# FTWearable.net
KiCad netlist of a schematic drawn in EAGLE
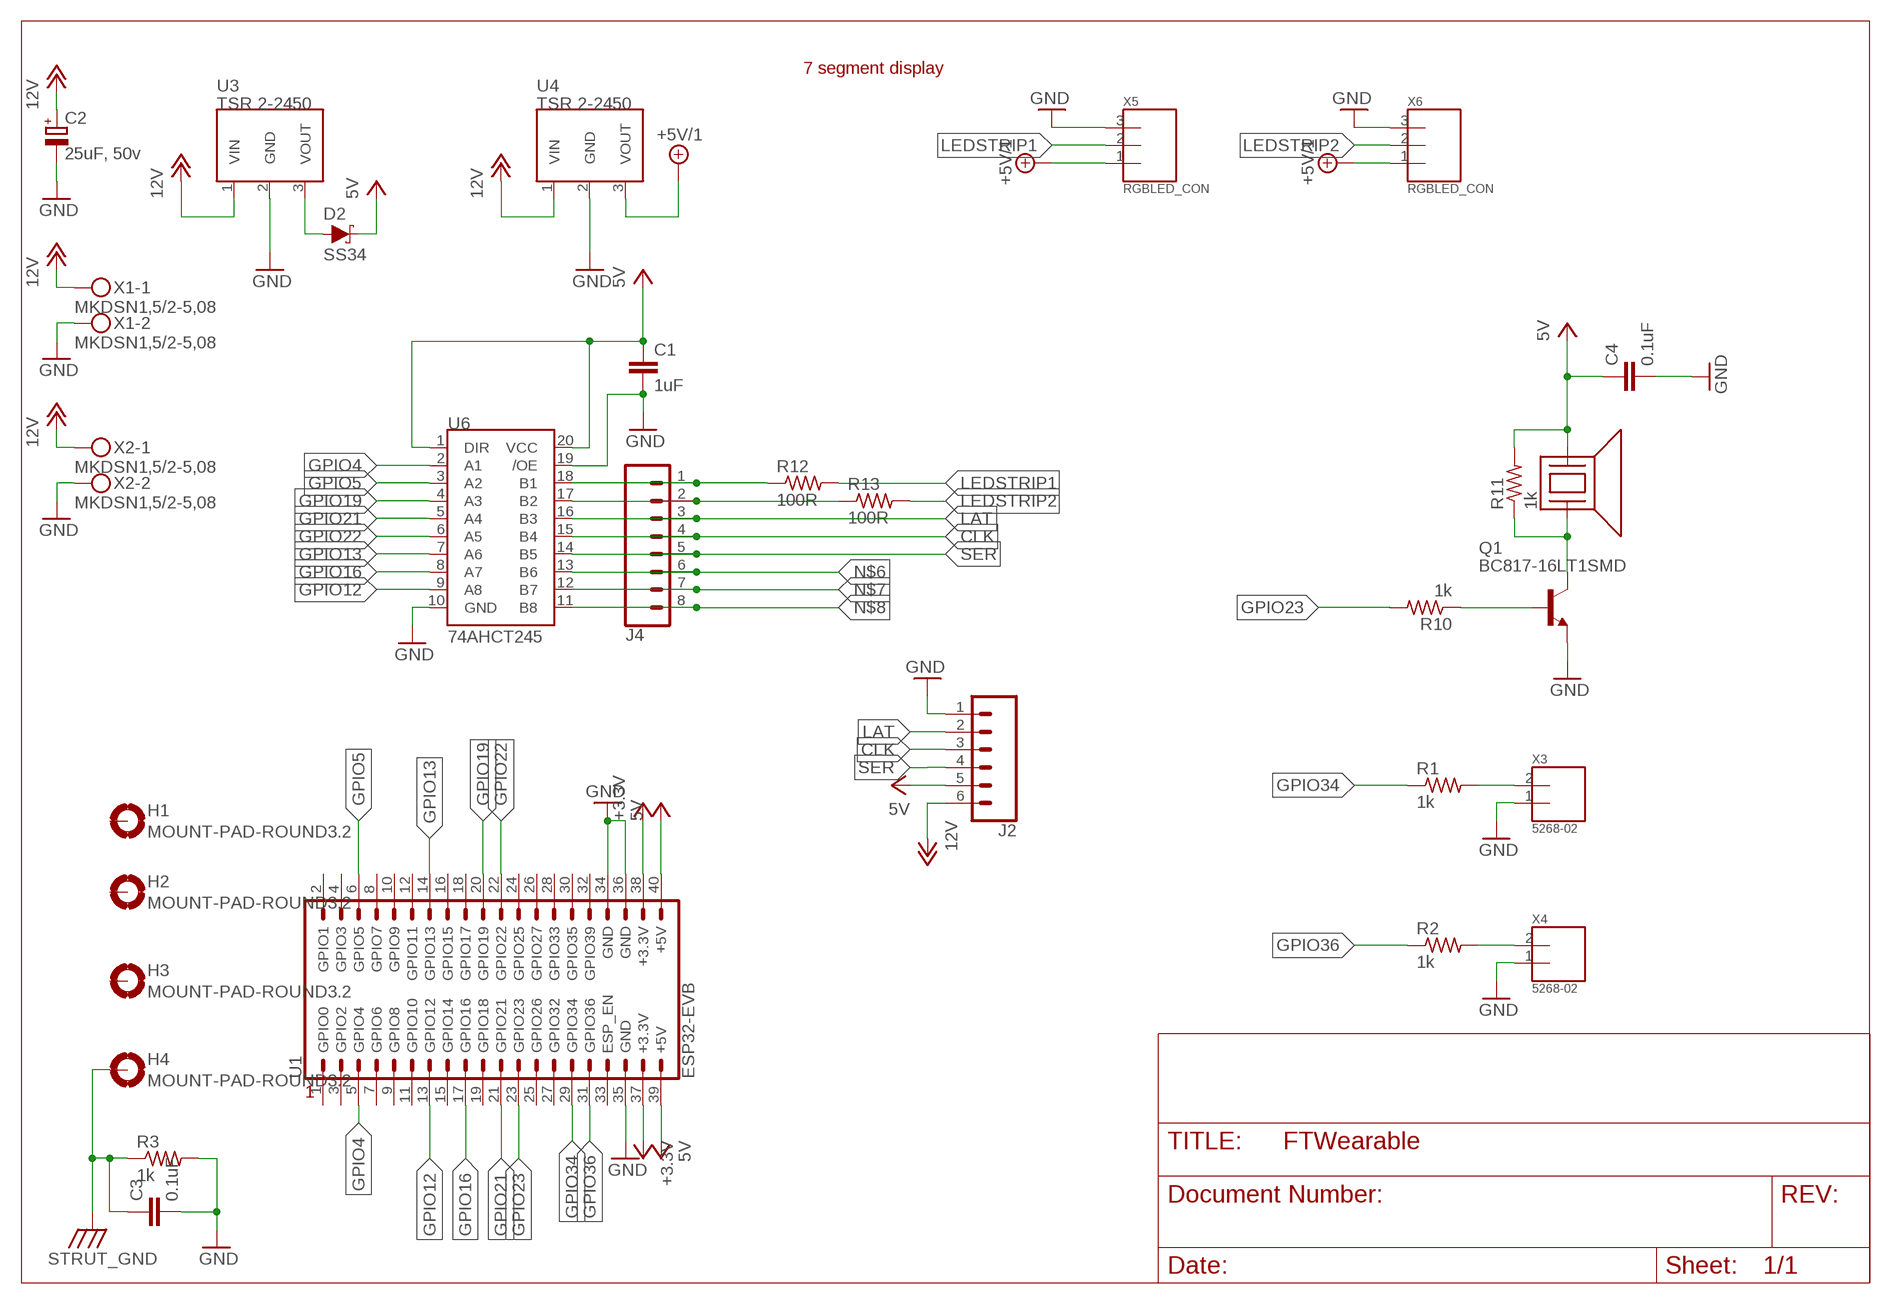
[diagram p0: schematic, sheet 1]

(export (version "E")
  (design (tool "Eeschema 10.0.6"))
  (components
    (comp (ref "C1")
      (value "1uF")
      (footprint "eagle-import:C0805(2012)_LEVEL_A")
      (libsource (lib "eagle-import") (part "C0805(2012)_LEVEL_A"))
    )
    (comp (ref "C2")
      (value "25uF, 50v")
      (footprint "eagle-import:PANASONIC_B_LEVEL_A")
      (libsource (lib "eagle-import") (part "C-POL-PB"))
    )
    (comp (ref "C3")
      (value "0.1uF")
      (footprint "eagle-import:C0603(1608)_LEVEL_A")
      (libsource (lib "eagle-import") (part "C0603(1608)_LEVEL_A"))
    )
    (comp (ref "C4")
      (value "0.1uF")
      (footprint "eagle-import:C0603(1608)_LEVEL_A")
      (libsource (lib "eagle-import") (part "C0603(1608)_LEVEL_A"))
    )
    (comp (ref "D2")
      (value "SS34")
      (footprint "eagle-import:DO-214BA")
      (libsource (lib "eagle-import") (part "DIODE-SCHOTTKY-LSM115JE3"))
    )
    (comp (ref "H1")
      (value "MOUNT-PAD-ROUND3.2")
      (footprint "eagle-import:3,2-PAD")
      (libsource (lib "eagle-import") (part "MOUNT-PAD-ROUND3.2"))
    )
    (comp (ref "H2")
      (value "MOUNT-PAD-ROUND3.2")
      (footprint "eagle-import:3,2-PAD")
      (libsource (lib "eagle-import") (part "MOUNT-PAD-ROUND3.2"))
    )
    (comp (ref "H3")
      (value "MOUNT-PAD-ROUND3.2")
      (footprint "eagle-import:3,2-PAD")
      (libsource (lib "eagle-import") (part "MOUNT-PAD-ROUND3.2"))
    )
    (comp (ref "H4")
      (value "MOUNT-PAD-ROUND3.2")
      (footprint "eagle-import:3,2-PAD")
      (libsource (lib "eagle-import") (part "MOUNT-PAD-ROUND3.2"))
    )
    (comp (ref "J2")
      (value "CONN_06SILK_FEMALE_PTH")
      (footprint "eagle-import:1X06")
      (libsource (lib "eagle-import") (part "CONN_06SILK_FEMALE_PTH"))
    )
    (comp (ref "J4")
      (value "CONN_08\"")
      (footprint "eagle-import:1X08")
      (libsource (lib "eagle-import") (part "CONN_08{dblquote}"))
    )
    (comp (ref "LED1")
      (value "SPARKFUN7SEGMENT")
      (footprint "eagle-import:SPARKFUN7SEGMENT")
      (libsource (lib "eagle-import") (part "SPARKFUN7SEGMENT"))
    )
    (comp (ref "Q1")
      (value "BC817-16LT1SMD")
      (footprint "eagle-import:SOT23-BEC")
      (libsource (lib "eagle-import") (part "BC817SMD-16LT1"))
    )
    (comp (ref "R1")
      (value "1k")
      (footprint "eagle-import:R0603(1608)_LEVEL_A")
      (libsource (lib "eagle-import") (part "R0603(1608)_LEVEL_A"))
    )
    (comp (ref "R2")
      (value "1k")
      (footprint "eagle-import:R0603(1608)_LEVEL_A")
      (libsource (lib "eagle-import") (part "R0603(1608)_LEVEL_A"))
    )
    (comp (ref "R3")
      (value "1k")
      (footprint "eagle-import:R0603(1608)_LEVEL_A")
      (libsource (lib "eagle-import") (part "R0603(1608)_LEVEL_A"))
    )
    (comp (ref "R10")
      (value "1k")
      (footprint "eagle-import:R0603(1608)_LEVEL_A")
      (libsource (lib "eagle-import") (part "R0603(1608)_LEVEL_A"))
    )
    (comp (ref "R11")
      (value "1k")
      (footprint "eagle-import:R0603(1608)_LEVEL_A")
      (libsource (lib "eagle-import") (part "R0603(1608)_LEVEL_A"))
    )
    (comp (ref "R12")
      (value "100R")
      (footprint "eagle-import:R0603(1608)_LEVEL_A")
      (libsource (lib "eagle-import") (part "R0603(1608)_LEVEL_A"))
    )
    (comp (ref "R13")
      (value "100R")
      (footprint "eagle-import:R0603(1608)_LEVEL_A")
      (libsource (lib "eagle-import") (part "R0603(1608)_LEVEL_A"))
    )
    (comp (ref "U1")
      (value "ESP32-EVB")
      (footprint "eagle-import:ESP32-EVB")
      (libsource (lib "eagle-import") (part "ESP32-EVB"))
    )
    (comp (ref "U3")
      (value "TSR 2-2450")
      (footprint "eagle-import:TSR2")
      (libsource (lib "eagle-import") (part "TSR"))
    )
    (comp (ref "U4")
      (value "TSR 2-2450")
      (footprint "eagle-import:TSR2")
      (libsource (lib "eagle-import") (part "TSR"))
    )
    (comp (ref "U5")
      (value "BUZZER")
      (footprint "eagle-import:PS1240")
      (libsource (lib "eagle-import") (part "BUZZER"))
    )
    (comp (ref "U6")
      (value "74AHCT245")
      (footprint "eagle-import:TSSOP-20_LEVEL_A")
      (libsource (lib "eagle-import") (part "74AHCT245"))
    )
    (comp (ref "X1")
      (value "MKDSN1,5/2-5,08")
      (footprint "eagle-import:MKDSN1,5_2-5,08")
      (libsource (lib "eagle-import") (part "MKDSN1,5/2-5,08"))
    )
    (comp (ref "X2")
      (value "MKDSN1,5/2-5,08")
      (footprint "eagle-import:MKDSN1,5_2-5,08")
      (libsource (lib "eagle-import") (part "MKDSN1,5/2-5,08"))
    )
    (comp (ref "X3")
      (value "5268-02")
      (footprint "eagle-import:5628-02")
      (libsource (lib "eagle-import") (part "5268-02"))
    )
    (comp (ref "X4")
      (value "5268-02")
      (footprint "eagle-import:5628-02")
      (libsource (lib "eagle-import") (part "5268-02"))
    )
    (comp (ref "X5")
      (value "RGBLED_CON")
      (footprint "eagle-import:RGBLED_CON")
      (libsource (lib "eagle-import") (part "RGBLED_CON"))
    )
    (comp (ref "X6")
      (value "RGBLED_CON")
      (footprint "eagle-import:RGBLED_CON")
      (libsource (lib "eagle-import") (part "RGBLED_CON"))
    )
  )
  (nets
    (net (code "1") (name "+3.3V") (class "Default")
      (node (ref "U1") (pin "37") (pinfunction "+3.3V_37") (pintype "passive"))
      (node (ref "U1") (pin "38") (pinfunction "+3.3V_38") (pintype "passive"))
    )
    (net (code "2") (name "+5V{slash}1") (class "Default")
      (node (ref "U4") (pin "3") (pinfunction "VOUT_3") (pintype "bidirectional"))
      (node (ref "X5") (pin "1") (pinfunction "1_1") (pintype "bidirectional"))
      (node (ref "X6") (pin "1") (pinfunction "1_1") (pintype "bidirectional"))
    )
    (net (code "3") (name "5V") (class "Default")
      (node (ref "C1") (pin "1") (pinfunction "1_1") (pintype "passive"))
      (node (ref "C4") (pin "1") (pinfunction "1_1") (pintype "passive"))
      (node (ref "D2") (pin "C") (pinfunction "C_C") (pintype "passive"))
      (node (ref "J2") (pin "5") (pinfunction "5_5") (pintype "passive"))
      (node (ref "R11") (pin "2") (pinfunction "2_2") (pintype "passive"))
      (node (ref "U1") (pin "39") (pinfunction "+5V_39") (pintype "passive"))
      (node (ref "U1") (pin "40") (pinfunction "+5V_40") (pintype "passive"))
      (node (ref "U5") (pin "1") (pinfunction "P$1_1") (pintype "bidirectional"))
      (node (ref "U6") (pin "1") (pinfunction "DIR_1") (pintype "bidirectional"))
      (node (ref "U6") (pin "20") (pinfunction "VCC_20") (pintype "bidirectional"))
    )
    (net (code "4") (name "12V") (class "Default")
      (node (ref "C2") (pin "1") (pinfunction "+_1") (pintype "passive"))
      (node (ref "J2") (pin "6") (pinfunction "6_6") (pintype "passive"))
      (node (ref "U3") (pin "1") (pinfunction "VIN_1") (pintype "bidirectional"))
      (node (ref "U4") (pin "1") (pinfunction "VIN_1") (pintype "bidirectional"))
      (node (ref "X1") (pin "1") (pinfunction "KL_1") (pintype "passive"))
      (node (ref "X2") (pin "1") (pinfunction "KL_1") (pintype "passive"))
    )
    (net (code "5") (name "CLK") (class "Default")
      (node (ref "J2") (pin "3") (pinfunction "3_3") (pintype "passive"))
      (node (ref "J4") (pin "4") (pinfunction "4_4") (pintype "passive"))
      (node (ref "U6") (pin "15") (pinfunction "B4_15") (pintype "bidirectional"))
    )
    (net (code "6") (name "GND") (class "Default")
      (node (ref "C1") (pin "2") (pinfunction "2_2") (pintype "passive"))
      (node (ref "C2") (pin "2") (pinfunction "-_2") (pintype "passive"))
      (node (ref "C3") (pin "2") (pinfunction "2_2") (pintype "passive"))
      (node (ref "C4") (pin "2") (pinfunction "2_2") (pintype "passive"))
      (node (ref "J2") (pin "1") (pinfunction "1_1") (pintype "passive"))
      (node (ref "Q1") (pin "E") (pinfunction "E_E") (pintype "passive"))
      (node (ref "R3") (pin "2") (pinfunction "2_2") (pintype "passive"))
      (node (ref "U1") (pin "34") (pinfunction "GND_34") (pintype "passive"))
      (node (ref "U1") (pin "35") (pinfunction "GND_35") (pintype "passive"))
      (node (ref "U1") (pin "36") (pinfunction "GND_36") (pintype "passive"))
      (node (ref "U3") (pin "2") (pinfunction "GND_2") (pintype "bidirectional"))
      (node (ref "U4") (pin "2") (pinfunction "GND_2") (pintype "bidirectional"))
      (node (ref "U6") (pin "10") (pinfunction "GND_10") (pintype "bidirectional"))
      (node (ref "U6") (pin "19") (pinfunction "/OE_19") (pintype "bidirectional"))
      (node (ref "X1") (pin "2") (pinfunction "KL_2") (pintype "passive"))
      (node (ref "X2") (pin "2") (pinfunction "KL_2") (pintype "passive"))
      (node (ref "X3") (pin "1") (pinfunction "1_1") (pintype "bidirectional"))
      (node (ref "X4") (pin "1") (pinfunction "1_1") (pintype "bidirectional"))
      (node (ref "X5") (pin "3") (pinfunction "3_3") (pintype "bidirectional"))
      (node (ref "X6") (pin "3") (pinfunction "3_3") (pintype "bidirectional"))
    )
    (net (code "7") (name "GPIO4") (class "Default")
      (node (ref "U1") (pin "5") (pinfunction "GPIO4_5") (pintype "passive"))
      (node (ref "U6") (pin "2") (pinfunction "A1_2") (pintype "bidirectional"))
    )
    (net (code "8") (name "GPIO5") (class "Default")
      (node (ref "U1") (pin "6") (pinfunction "GPIO5_6") (pintype "passive"))
      (node (ref "U6") (pin "3") (pinfunction "A2_3") (pintype "bidirectional"))
    )
    (net (code "9") (name "GPIO12") (class "Default")
      (node (ref "U1") (pin "13") (pinfunction "GPIO12_13") (pintype "passive"))
      (node (ref "U6") (pin "9") (pinfunction "A8_9") (pintype "bidirectional"))
    )
    (net (code "10") (name "GPIO13") (class "Default")
      (node (ref "U1") (pin "14") (pinfunction "GPIO13_14") (pintype "passive"))
      (node (ref "U6") (pin "7") (pinfunction "A6_7") (pintype "bidirectional"))
    )
    (net (code "11") (name "GPIO16") (class "Default")
      (node (ref "U1") (pin "17") (pinfunction "GPIO16_17") (pintype "passive"))
      (node (ref "U6") (pin "8") (pinfunction "A7_8") (pintype "bidirectional"))
    )
    (net (code "12") (name "GPIO19") (class "Default")
      (node (ref "U1") (pin "20") (pinfunction "GPIO19_20") (pintype "passive"))
      (node (ref "U6") (pin "4") (pinfunction "A3_4") (pintype "bidirectional"))
    )
    (net (code "13") (name "GPIO21") (class "Default")
      (node (ref "U1") (pin "21") (pinfunction "GPIO21_21") (pintype "passive"))
      (node (ref "U6") (pin "5") (pinfunction "A4_5") (pintype "bidirectional"))
    )
    (net (code "14") (name "GPIO22") (class "Default")
      (node (ref "U1") (pin "22") (pinfunction "GPIO22_22") (pintype "passive"))
      (node (ref "U6") (pin "6") (pinfunction "A5_6") (pintype "bidirectional"))
    )
    (net (code "15") (name "GPIO23") (class "Default")
      (node (ref "R10") (pin "2") (pinfunction "2_2") (pintype "passive"))
      (node (ref "U1") (pin "23") (pinfunction "GPIO23_23") (pintype "passive"))
    )
    (net (code "16") (name "GPIO34") (class "Default")
      (node (ref "R1") (pin "1") (pinfunction "1_1") (pintype "passive"))
      (node (ref "U1") (pin "29") (pinfunction "GPIO34_29") (pintype "passive"))
    )
    (net (code "17") (name "GPIO36") (class "Default")
      (node (ref "R2") (pin "1") (pinfunction "1_1") (pintype "passive"))
      (node (ref "U1") (pin "31") (pinfunction "GPIO36_31") (pintype "passive"))
    )
    (net (code "18") (name "LAT") (class "Default")
      (node (ref "J2") (pin "2") (pinfunction "2_2") (pintype "passive"))
      (node (ref "J4") (pin "3") (pinfunction "3_3") (pintype "passive"))
      (node (ref "U6") (pin "16") (pinfunction "B3_16") (pintype "bidirectional"))
    )
    (net (code "19") (name "LEDSTRIP1") (class "Default")
      (node (ref "R12") (pin "2") (pinfunction "2_2") (pintype "passive"))
      (node (ref "X5") (pin "2") (pinfunction "2_2") (pintype "bidirectional"))
    )
    (net (code "20") (name "LEDSTRIP2") (class "Default")
      (node (ref "R13") (pin "2") (pinfunction "2_2") (pintype "passive"))
      (node (ref "X6") (pin "2") (pinfunction "2_2") (pintype "bidirectional"))
    )
    (net (code "21") (name "N$6") (class "Default")
      (node (ref "J4") (pin "6") (pinfunction "6_6") (pintype "passive"))
      (node (ref "U6") (pin "13") (pinfunction "B6_13") (pintype "bidirectional"))
    )
    (net (code "22") (name "N$7") (class "Default")
      (node (ref "J4") (pin "7") (pinfunction "7_7") (pintype "passive"))
      (node (ref "U6") (pin "12") (pinfunction "B7_12") (pintype "bidirectional"))
    )
    (net (code "23") (name "N$8") (class "Default")
      (node (ref "J4") (pin "8") (pinfunction "8_8") (pintype "passive"))
      (node (ref "U6") (pin "11") (pinfunction "B8_11") (pintype "bidirectional"))
    )
    (net (code "24") (name "Net-(Q1-PadB)") (class "Default")
      (node (ref "Q1") (pin "B") (pinfunction "B_B") (pintype "passive"))
      (node (ref "R10") (pin "1") (pinfunction "1_1") (pintype "passive"))
    )
    (net (code "25") (name "Net-(R1-Pad2)") (class "Default")
      (node (ref "R1") (pin "2") (pinfunction "2_2") (pintype "passive"))
      (node (ref "X3") (pin "2") (pinfunction "2_2") (pintype "bidirectional"))
    )
    (net (code "26") (name "Net-(R2-Pad2)") (class "Default")
      (node (ref "R2") (pin "2") (pinfunction "2_2") (pintype "passive"))
      (node (ref "X4") (pin "2") (pinfunction "2_2") (pintype "bidirectional"))
    )
    (net (code "27") (name "Net-(U3-VOUT)") (class "Default")
      (node (ref "D2") (pin "A") (pinfunction "A_A") (pintype "passive"))
      (node (ref "U3") (pin "3") (pinfunction "VOUT_3") (pintype "bidirectional"))
    )
    (net (code "28") (name "Net-(U5-P$2)") (class "Default")
      (node (ref "Q1") (pin "C") (pinfunction "C_C") (pintype "passive"))
      (node (ref "R11") (pin "1") (pinfunction "1_1") (pintype "passive"))
      (node (ref "U5") (pin "2") (pinfunction "P$2_2") (pintype "bidirectional"))
    )
    (net (code "29") (name "Net-(U6-B1)") (class "Default")
      (node (ref "J4") (pin "1") (pinfunction "1_1") (pintype "passive"))
      (node (ref "R12") (pin "1") (pinfunction "1_1") (pintype "passive"))
      (node (ref "U6") (pin "18") (pinfunction "B1_18") (pintype "bidirectional"))
    )
    (net (code "30") (name "Net-(U6-B2)") (class "Default")
      (node (ref "J4") (pin "2") (pinfunction "2_2") (pintype "passive"))
      (node (ref "R13") (pin "1") (pinfunction "1_1") (pintype "passive"))
      (node (ref "U6") (pin "17") (pinfunction "B2_17") (pintype "bidirectional"))
    )
    (net (code "31") (name "SER") (class "Default")
      (node (ref "J2") (pin "4") (pinfunction "4_4") (pintype "passive"))
      (node (ref "J4") (pin "5") (pinfunction "5_5") (pintype "passive"))
      (node (ref "U6") (pin "14") (pinfunction "B5_14") (pintype "bidirectional"))
    )
    (net (code "32") (name "STRUT_GND") (class "Default")
      (node (ref "C3") (pin "1") (pinfunction "1_1") (pintype "passive"))
      (node (ref "H4") (pin "B3,2") (pinfunction "MOUNT_B3,2") (pintype "passive"))
      (node (ref "R3") (pin "1") (pinfunction "1_1") (pintype "passive"))
    )
    (net (code "33") (name "unconnected-(H1-MOUNT-PadB3,2)") (class "Default")
      (node (ref "H1") (pin "B3,2") (pinfunction "MOUNT_B3,2") (pintype "passive"))
    )
    (net (code "34") (name "unconnected-(H2-MOUNT-PadB3,2)") (class "Default")
      (node (ref "H2") (pin "B3,2") (pinfunction "MOUNT_B3,2") (pintype "passive"))
    )
    (net (code "35") (name "unconnected-(H3-MOUNT-PadB3,2)") (class "Default")
      (node (ref "H3") (pin "B3,2") (pinfunction "MOUNT_B3,2") (pintype "passive"))
    )
    (net (code "36") (name "unconnected-(U1-ESP_EN-Pad33)") (class "Default")
      (node (ref "U1") (pin "33") (pinfunction "ESP_EN_33") (pintype "passive"))
    )
    (net (code "37") (name "unconnected-(U1-GPIO0-Pad1)") (class "Default")
      (node (ref "U1") (pin "1") (pinfunction "GPIO0_1") (pintype "passive"))
    )
    (net (code "38") (name "unconnected-(U1-GPIO1-Pad2)") (class "Default")
      (node (ref "U1") (pin "2") (pinfunction "GPIO1_2") (pintype "passive"))
    )
    (net (code "39") (name "unconnected-(U1-GPIO2-Pad3)") (class "Default")
      (node (ref "U1") (pin "3") (pinfunction "GPIO2_3") (pintype "passive"))
    )
    (net (code "40") (name "unconnected-(U1-GPIO3-Pad4)") (class "Default")
      (node (ref "U1") (pin "4") (pinfunction "GPIO3_4") (pintype "passive"))
    )
    (net (code "41") (name "unconnected-(U1-GPIO6-Pad7)") (class "Default")
      (node (ref "U1") (pin "7") (pinfunction "GPIO6_7") (pintype "passive"))
    )
    (net (code "42") (name "unconnected-(U1-GPIO7-Pad8)") (class "Default")
      (node (ref "U1") (pin "8") (pinfunction "GPIO7_8") (pintype "passive"))
    )
    (net (code "43") (name "unconnected-(U1-GPIO8-Pad9)") (class "Default")
      (node (ref "U1") (pin "9") (pinfunction "GPIO8_9") (pintype "passive"))
    )
    (net (code "44") (name "unconnected-(U1-GPIO9-Pad10)") (class "Default")
      (node (ref "U1") (pin "10") (pinfunction "GPIO9_10") (pintype "passive"))
    )
    (net (code "45") (name "unconnected-(U1-GPIO10-Pad11)") (class "Default")
      (node (ref "U1") (pin "11") (pinfunction "GPIO10_11") (pintype "passive"))
    )
    (net (code "46") (name "unconnected-(U1-GPIO11-Pad12)") (class "Default")
      (node (ref "U1") (pin "12") (pinfunction "GPIO11_12") (pintype "passive"))
    )
    (net (code "47") (name "unconnected-(U1-GPIO14-Pad15)") (class "Default")
      (node (ref "U1") (pin "15") (pinfunction "GPIO14_15") (pintype "passive"))
    )
    (net (code "48") (name "unconnected-(U1-GPIO15-Pad16)") (class "Default")
      (node (ref "U1") (pin "16") (pinfunction "GPIO15_16") (pintype "passive"))
    )
    (net (code "49") (name "unconnected-(U1-GPIO17-Pad18)") (class "Default")
      (node (ref "U1") (pin "18") (pinfunction "GPIO17_18") (pintype "passive"))
    )
    (net (code "50") (name "unconnected-(U1-GPIO18-Pad19)") (class "Default")
      (node (ref "U1") (pin "19") (pinfunction "GPIO18_19") (pintype "passive"))
    )
    (net (code "51") (name "unconnected-(U1-GPIO25-Pad24)") (class "Default")
      (node (ref "U1") (pin "24") (pinfunction "GPIO25_24") (pintype "passive"))
    )
    (net (code "52") (name "unconnected-(U1-GPIO26-Pad25)") (class "Default")
      (node (ref "U1") (pin "25") (pinfunction "GPIO26_25") (pintype "passive"))
    )
    (net (code "53") (name "unconnected-(U1-GPIO27-Pad26)") (class "Default")
      (node (ref "U1") (pin "26") (pinfunction "GPIO27_26") (pintype "passive"))
    )
    (net (code "54") (name "unconnected-(U1-GPIO32-Pad27)") (class "Default")
      (node (ref "U1") (pin "27") (pinfunction "GPIO32_27") (pintype "passive"))
    )
    (net (code "55") (name "unconnected-(U1-GPIO33-Pad28)") (class "Default")
      (node (ref "U1") (pin "28") (pinfunction "GPIO33_28") (pintype "passive"))
    )
    (net (code "56") (name "unconnected-(U1-GPIO35-Pad30)") (class "Default")
      (node (ref "U1") (pin "30") (pinfunction "GPIO35_30") (pintype "passive"))
    )
    (net (code "57") (name "unconnected-(U1-GPIO39-Pad32)") (class "Default")
      (node (ref "U1") (pin "32") (pinfunction "GPIO39_32") (pintype "passive"))
    )
  )
)
